# mux2.net
KiCad netlist of a schematic drawn in EAGLE
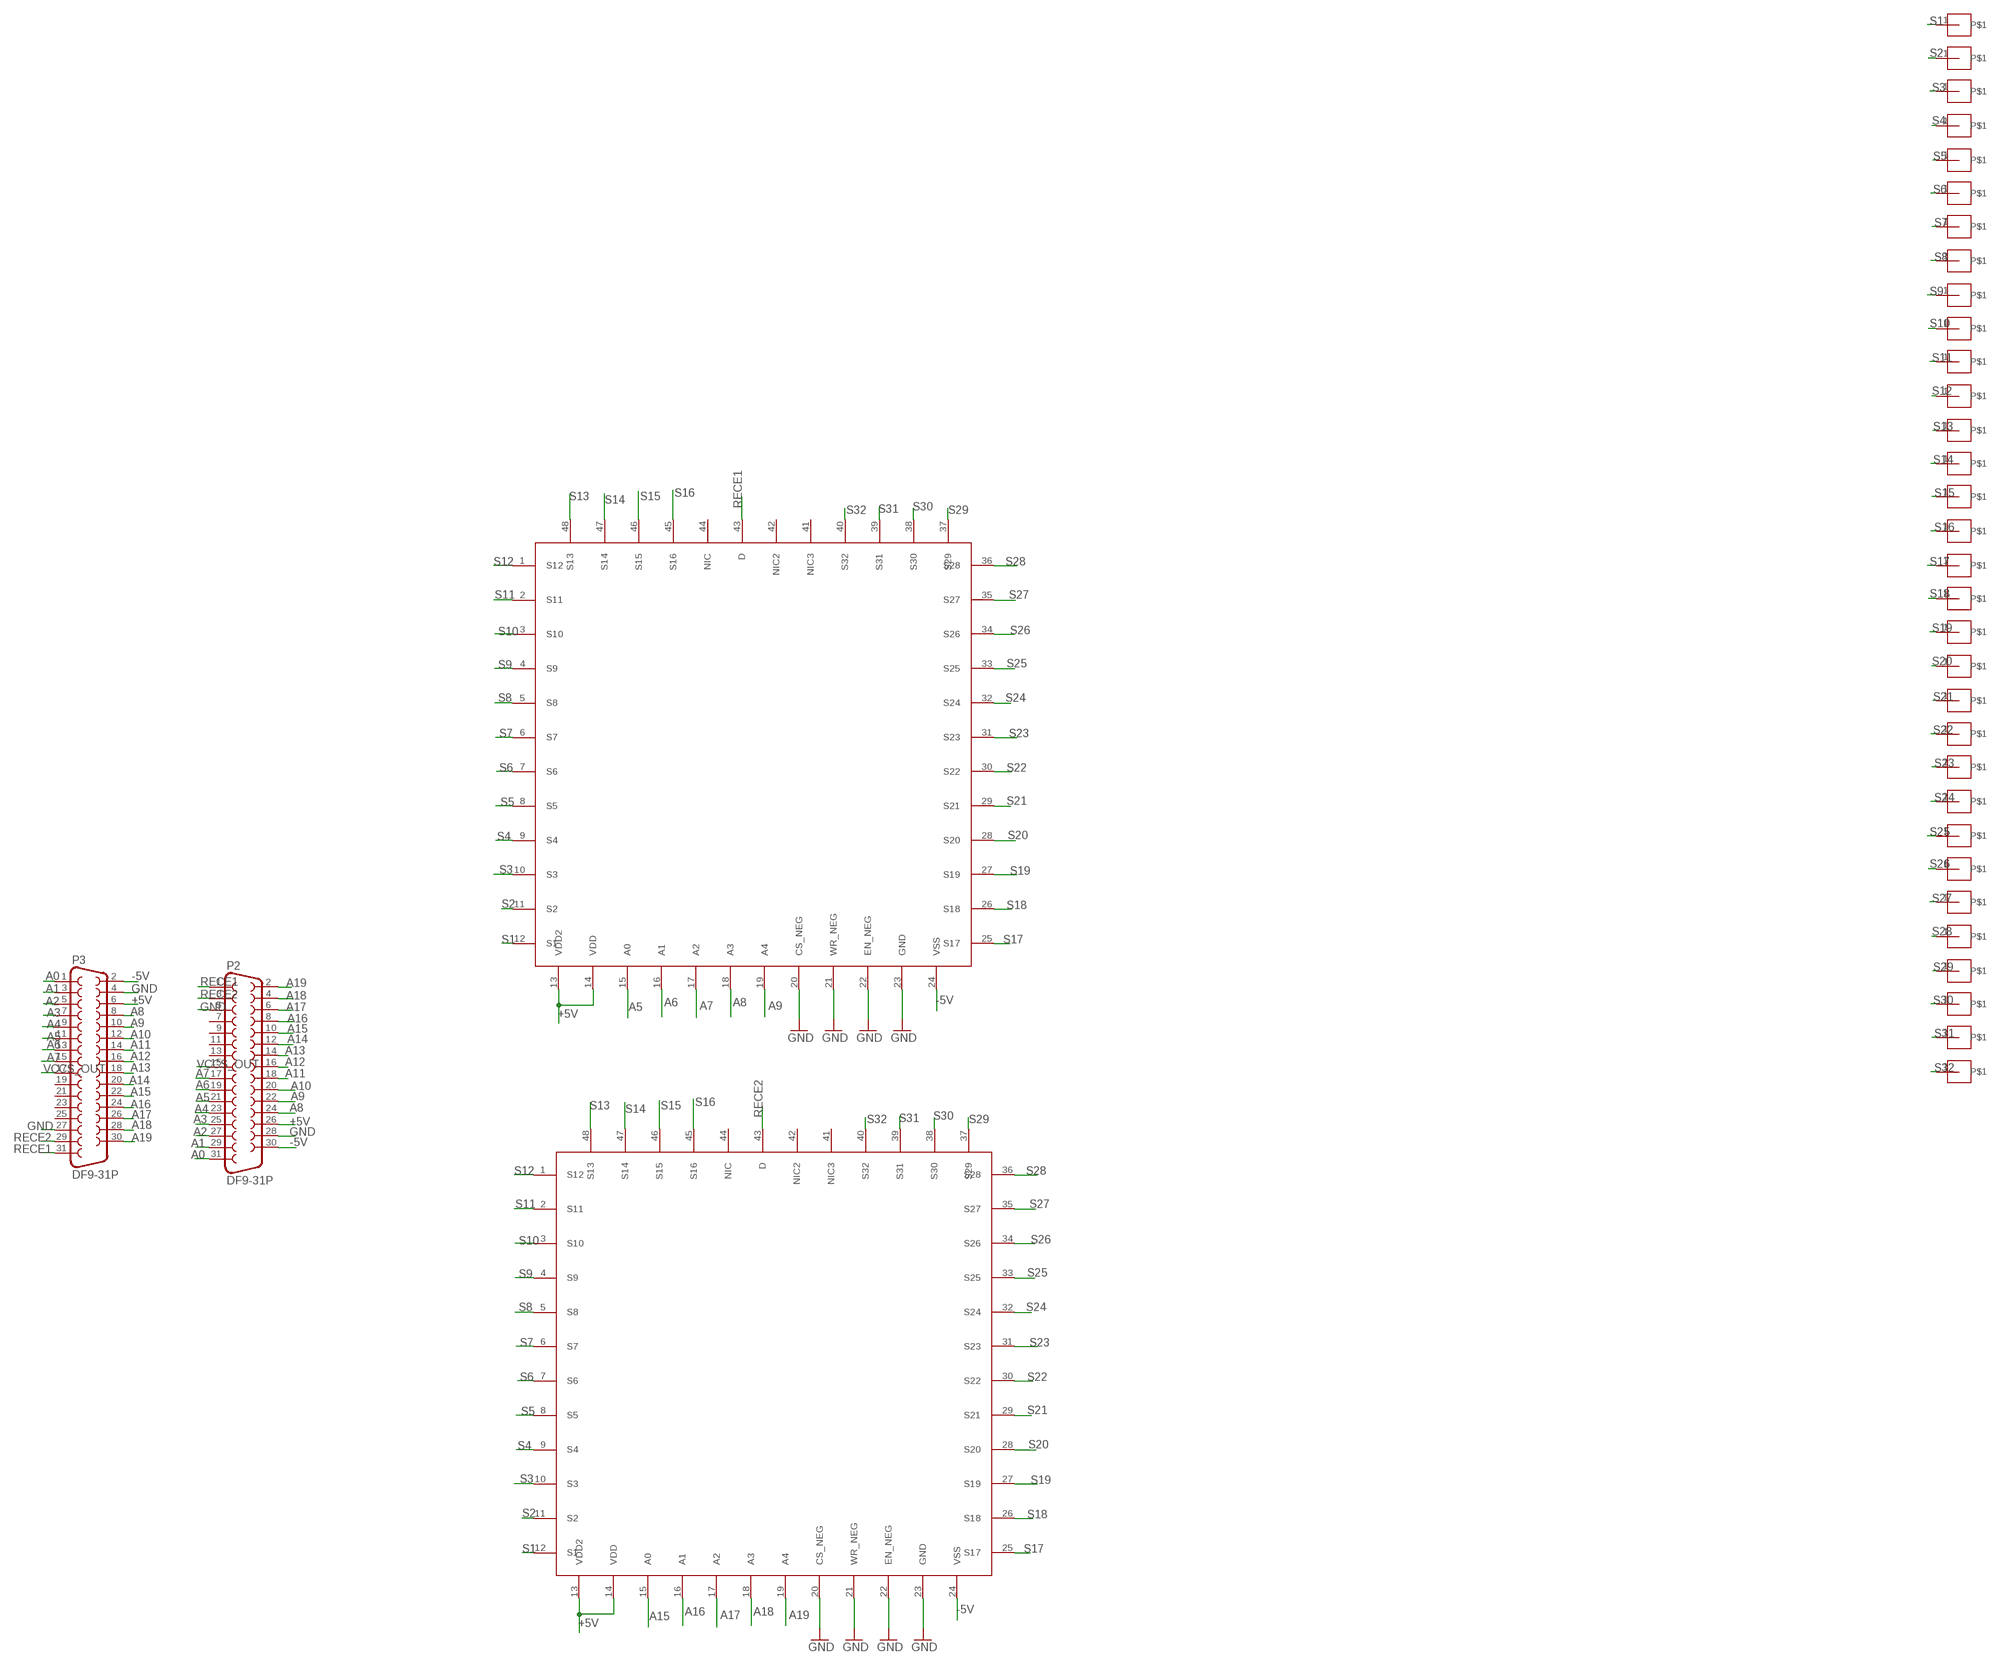
[diagram p0: schematic, sheet 1]

(export (version "E")
  (design (tool "Eeschema 10.0.6"))
  (components
    (comp (ref "P2")
      (value "DF9-31P")
      (footprint "eagle-import:DF9-31P")
      (libsource (lib "eagle-import") (part "DF9-31P"))
    )
    (comp (ref "P3")
      (value "DF9-31P")
      (footprint "eagle-import:DF9-31P")
      (libsource (lib "eagle-import") (part "DF9-31P"))
    )
    (comp (ref "U$25")
      (value "M01")
      (footprint "eagle-import:M01")
      (libsource (lib "eagle-import") (part "M01"))
    )
    (comp (ref "U$26")
      (value "M01")
      (footprint "eagle-import:M01")
      (libsource (lib "eagle-import") (part "M01"))
    )
    (comp (ref "U$27")
      (value "M01")
      (footprint "eagle-import:M01")
      (libsource (lib "eagle-import") (part "M01"))
    )
    (comp (ref "U$28")
      (value "M01")
      (footprint "eagle-import:M01")
      (libsource (lib "eagle-import") (part "M01"))
    )
    (comp (ref "U$29")
      (value "M01")
      (footprint "eagle-import:M01")
      (libsource (lib "eagle-import") (part "M01"))
    )
    (comp (ref "U$30")
      (value "M01")
      (footprint "eagle-import:M01")
      (libsource (lib "eagle-import") (part "M01"))
    )
    (comp (ref "U$31")
      (value "M01")
      (footprint "eagle-import:M01")
      (libsource (lib "eagle-import") (part "M01"))
    )
    (comp (ref "U$32")
      (value "M01")
      (footprint "eagle-import:M01")
      (libsource (lib "eagle-import") (part "M01"))
    )
    (comp (ref "U$33")
      (value "M01")
      (footprint "eagle-import:M01")
      (libsource (lib "eagle-import") (part "M01"))
    )
    (comp (ref "U$34")
      (value "M01")
      (footprint "eagle-import:M01")
      (libsource (lib "eagle-import") (part "M01"))
    )
    (comp (ref "U$35")
      (value "M01")
      (footprint "eagle-import:M01")
      (libsource (lib "eagle-import") (part "M01"))
    )
    (comp (ref "U$36")
      (value "M01")
      (footprint "eagle-import:M01")
      (libsource (lib "eagle-import") (part "M01"))
    )
    (comp (ref "U$37")
      (value "M01")
      (footprint "eagle-import:M01")
      (libsource (lib "eagle-import") (part "M01"))
    )
    (comp (ref "U$38")
      (value "M01")
      (footprint "eagle-import:M01")
      (libsource (lib "eagle-import") (part "M01"))
    )
    (comp (ref "U$39")
      (value "M01")
      (footprint "eagle-import:M01")
      (libsource (lib "eagle-import") (part "M01"))
    )
    (comp (ref "U$40")
      (value "M01")
      (footprint "eagle-import:M01")
      (libsource (lib "eagle-import") (part "M01"))
    )
    (comp (ref "U$41")
      (value "M01")
      (footprint "eagle-import:M01")
      (libsource (lib "eagle-import") (part "M01"))
    )
    (comp (ref "U$42")
      (value "M01")
      (footprint "eagle-import:M01")
      (libsource (lib "eagle-import") (part "M01"))
    )
    (comp (ref "U$43")
      (value "M01")
      (footprint "eagle-import:M01")
      (libsource (lib "eagle-import") (part "M01"))
    )
    (comp (ref "U$44")
      (value "M01")
      (footprint "eagle-import:M01")
      (libsource (lib "eagle-import") (part "M01"))
    )
    (comp (ref "U$45")
      (value "M01")
      (footprint "eagle-import:M01")
      (libsource (lib "eagle-import") (part "M01"))
    )
    (comp (ref "U$46")
      (value "M01")
      (footprint "eagle-import:M01")
      (libsource (lib "eagle-import") (part "M01"))
    )
    (comp (ref "U$47")
      (value "M01")
      (footprint "eagle-import:M01")
      (libsource (lib "eagle-import") (part "M01"))
    )
    (comp (ref "U$48")
      (value "M01")
      (footprint "eagle-import:M01")
      (libsource (lib "eagle-import") (part "M01"))
    )
    (comp (ref "U$49")
      (value "M01")
      (footprint "eagle-import:M01")
      (libsource (lib "eagle-import") (part "M01"))
    )
    (comp (ref "U$50")
      (value "M01")
      (footprint "eagle-import:M01")
      (libsource (lib "eagle-import") (part "M01"))
    )
    (comp (ref "U$51")
      (value "M01")
      (footprint "eagle-import:M01")
      (libsource (lib "eagle-import") (part "M01"))
    )
    (comp (ref "U$52")
      (value "M01")
      (footprint "eagle-import:M01")
      (libsource (lib "eagle-import") (part "M01"))
    )
    (comp (ref "U$53")
      (value "M01")
      (footprint "eagle-import:M01")
      (libsource (lib "eagle-import") (part "M01"))
    )
    (comp (ref "U$54")
      (value "M01")
      (footprint "eagle-import:M01")
      (libsource (lib "eagle-import") (part "M01"))
    )
    (comp (ref "U$55")
      (value "M01")
      (footprint "eagle-import:M01")
      (libsource (lib "eagle-import") (part "M01"))
    )
    (comp (ref "U$56")
      (value "M01")
      (footprint "eagle-import:M01")
      (libsource (lib "eagle-import") (part "M01"))
    )
    (comp (ref "U$73")
      (value "ADG732")
      (footprint "eagle-import:TQFP48")
      (libsource (lib "eagle-import") (part "ADG732"))
    )
    (comp (ref "U$74")
      (value "ADG732")
      (footprint "eagle-import:TQFP48")
      (libsource (lib "eagle-import") (part "ADG732"))
    )
  )
  (nets
    (net (code "1") (name "/+5V") (class "Default")
      (node (ref "P2") (pin "26") (pinfunction "26_26") (pintype "passive"))
      (node (ref "P3") (pin "6") (pinfunction "6_6") (pintype "passive"))
      (node (ref "U$73") (pin "13") (pinfunction "VDD2_13") (pintype "bidirectional"))
      (node (ref "U$73") (pin "14") (pinfunction "VDD_14") (pintype "bidirectional"))
      (node (ref "U$74") (pin "13") (pinfunction "VDD2_13") (pintype "bidirectional"))
      (node (ref "U$74") (pin "14") (pinfunction "VDD_14") (pintype "bidirectional"))
    )
    (net (code "2") (name "/-5V") (class "Default")
      (node (ref "P2") (pin "30") (pinfunction "30_30") (pintype "passive"))
      (node (ref "P3") (pin "2") (pinfunction "2_2") (pintype "passive"))
      (node (ref "U$73") (pin "24") (pinfunction "VSS_24") (pintype "bidirectional"))
      (node (ref "U$74") (pin "24") (pinfunction "VSS_24") (pintype "bidirectional"))
    )
    (net (code "3") (name "/A0") (class "Default")
      (node (ref "P2") (pin "31") (pinfunction "31_31") (pintype "passive"))
      (node (ref "P3") (pin "1") (pinfunction "1_1") (pintype "passive"))
    )
    (net (code "4") (name "/A1") (class "Default")
      (node (ref "P2") (pin "29") (pinfunction "29_29") (pintype "passive"))
      (node (ref "P3") (pin "3") (pinfunction "3_3") (pintype "passive"))
    )
    (net (code "5") (name "/A2") (class "Default")
      (node (ref "P2") (pin "27") (pinfunction "27_27") (pintype "passive"))
      (node (ref "P3") (pin "5") (pinfunction "5_5") (pintype "passive"))
    )
    (net (code "6") (name "/A3") (class "Default")
      (node (ref "P2") (pin "25") (pinfunction "25_25") (pintype "passive"))
      (node (ref "P3") (pin "7") (pinfunction "7_7") (pintype "passive"))
    )
    (net (code "7") (name "/A4") (class "Default")
      (node (ref "P2") (pin "23") (pinfunction "23_23") (pintype "passive"))
      (node (ref "P3") (pin "9") (pinfunction "9_9") (pintype "passive"))
    )
    (net (code "8") (name "/A5") (class "Default")
      (node (ref "P2") (pin "21") (pinfunction "21_21") (pintype "passive"))
      (node (ref "P3") (pin "11") (pinfunction "11_11") (pintype "passive"))
      (node (ref "U$74") (pin "15") (pinfunction "A0_15") (pintype "bidirectional"))
    )
    (net (code "9") (name "/A6") (class "Default")
      (node (ref "P2") (pin "19") (pinfunction "19_19") (pintype "passive"))
      (node (ref "P3") (pin "13") (pinfunction "13_13") (pintype "passive"))
      (node (ref "U$74") (pin "16") (pinfunction "A1_16") (pintype "bidirectional"))
    )
    (net (code "10") (name "/A7") (class "Default")
      (node (ref "P2") (pin "17") (pinfunction "17_17") (pintype "passive"))
      (node (ref "P3") (pin "15") (pinfunction "15_15") (pintype "passive"))
      (node (ref "U$74") (pin "17") (pinfunction "A2_17") (pintype "bidirectional"))
    )
    (net (code "11") (name "/A8") (class "Default")
      (node (ref "P2") (pin "24") (pinfunction "24_24") (pintype "passive"))
      (node (ref "P3") (pin "8") (pinfunction "8_8") (pintype "passive"))
      (node (ref "U$74") (pin "18") (pinfunction "A3_18") (pintype "bidirectional"))
    )
    (net (code "12") (name "/A9") (class "Default")
      (node (ref "P2") (pin "22") (pinfunction "22_22") (pintype "passive"))
      (node (ref "P3") (pin "10") (pinfunction "10_10") (pintype "passive"))
      (node (ref "U$74") (pin "19") (pinfunction "A4_19") (pintype "bidirectional"))
    )
    (net (code "13") (name "/A10") (class "Default")
      (node (ref "P2") (pin "20") (pinfunction "20_20") (pintype "passive"))
      (node (ref "P3") (pin "12") (pinfunction "12_12") (pintype "passive"))
    )
    (net (code "14") (name "/A11") (class "Default")
      (node (ref "P2") (pin "18") (pinfunction "18_18") (pintype "passive"))
      (node (ref "P3") (pin "14") (pinfunction "14_14") (pintype "passive"))
    )
    (net (code "15") (name "/A12") (class "Default")
      (node (ref "P2") (pin "16") (pinfunction "16_16") (pintype "passive"))
      (node (ref "P3") (pin "16") (pinfunction "16_16") (pintype "passive"))
    )
    (net (code "16") (name "/A13") (class "Default")
      (node (ref "P2") (pin "14") (pinfunction "14_14") (pintype "passive"))
      (node (ref "P3") (pin "18") (pinfunction "18_18") (pintype "passive"))
    )
    (net (code "17") (name "/A14") (class "Default")
      (node (ref "P2") (pin "12") (pinfunction "12_12") (pintype "passive"))
      (node (ref "P3") (pin "20") (pinfunction "20_20") (pintype "passive"))
    )
    (net (code "18") (name "/A15") (class "Default")
      (node (ref "P2") (pin "10") (pinfunction "10_10") (pintype "passive"))
      (node (ref "P3") (pin "22") (pinfunction "22_22") (pintype "passive"))
      (node (ref "U$73") (pin "15") (pinfunction "A0_15") (pintype "bidirectional"))
    )
    (net (code "19") (name "/A16") (class "Default")
      (node (ref "P2") (pin "8") (pinfunction "8_8") (pintype "passive"))
      (node (ref "P3") (pin "24") (pinfunction "24_24") (pintype "passive"))
      (node (ref "U$73") (pin "16") (pinfunction "A1_16") (pintype "bidirectional"))
    )
    (net (code "20") (name "/A17") (class "Default")
      (node (ref "P2") (pin "6") (pinfunction "6_6") (pintype "passive"))
      (node (ref "P3") (pin "26") (pinfunction "26_26") (pintype "passive"))
      (node (ref "U$73") (pin "17") (pinfunction "A2_17") (pintype "bidirectional"))
    )
    (net (code "21") (name "/A18") (class "Default")
      (node (ref "P2") (pin "4") (pinfunction "4_4") (pintype "passive"))
      (node (ref "P3") (pin "28") (pinfunction "28_28") (pintype "passive"))
      (node (ref "U$73") (pin "18") (pinfunction "A3_18") (pintype "bidirectional"))
    )
    (net (code "22") (name "/A19") (class "Default")
      (node (ref "P2") (pin "2") (pinfunction "2_2") (pintype "passive"))
      (node (ref "P3") (pin "30") (pinfunction "30_30") (pintype "passive"))
      (node (ref "U$73") (pin "19") (pinfunction "A4_19") (pintype "bidirectional"))
    )
    (net (code "23") (name "/RECE1") (class "Default")
      (node (ref "P2") (pin "1") (pinfunction "1_1") (pintype "passive"))
      (node (ref "P3") (pin "31") (pinfunction "31_31") (pintype "passive"))
      (node (ref "U$74") (pin "43") (pinfunction "D_43") (pintype "bidirectional"))
    )
    (net (code "24") (name "/RECE2") (class "Default")
      (node (ref "P2") (pin "3") (pinfunction "3_3") (pintype "passive"))
      (node (ref "P3") (pin "29") (pinfunction "29_29") (pintype "passive"))
      (node (ref "U$73") (pin "43") (pinfunction "D_43") (pintype "bidirectional"))
    )
    (net (code "25") (name "/S1") (class "Default")
      (node (ref "U$25") (pin "1") (pinfunction "P$1_1") (pintype "bidirectional"))
      (node (ref "U$73") (pin "12") (pinfunction "S1_12") (pintype "bidirectional"))
      (node (ref "U$74") (pin "12") (pinfunction "S1_12") (pintype "bidirectional"))
    )
    (net (code "26") (name "/S2") (class "Default")
      (node (ref "U$26") (pin "1") (pinfunction "P$1_1") (pintype "bidirectional"))
      (node (ref "U$73") (pin "11") (pinfunction "S2_11") (pintype "bidirectional"))
      (node (ref "U$74") (pin "11") (pinfunction "S2_11") (pintype "bidirectional"))
    )
    (net (code "27") (name "/S3") (class "Default")
      (node (ref "U$27") (pin "1") (pinfunction "P$1_1") (pintype "bidirectional"))
      (node (ref "U$73") (pin "10") (pinfunction "S3_10") (pintype "bidirectional"))
      (node (ref "U$74") (pin "10") (pinfunction "S3_10") (pintype "bidirectional"))
    )
    (net (code "28") (name "/S4") (class "Default")
      (node (ref "U$28") (pin "1") (pinfunction "P$1_1") (pintype "bidirectional"))
      (node (ref "U$73") (pin "9") (pinfunction "S4_9") (pintype "bidirectional"))
      (node (ref "U$74") (pin "9") (pinfunction "S4_9") (pintype "bidirectional"))
    )
    (net (code "29") (name "/S5") (class "Default")
      (node (ref "U$29") (pin "1") (pinfunction "P$1_1") (pintype "bidirectional"))
      (node (ref "U$73") (pin "8") (pinfunction "S5_8") (pintype "bidirectional"))
      (node (ref "U$74") (pin "8") (pinfunction "S5_8") (pintype "bidirectional"))
    )
    (net (code "30") (name "/S6") (class "Default")
      (node (ref "U$30") (pin "1") (pinfunction "P$1_1") (pintype "bidirectional"))
      (node (ref "U$73") (pin "7") (pinfunction "S6_7") (pintype "bidirectional"))
      (node (ref "U$74") (pin "7") (pinfunction "S6_7") (pintype "bidirectional"))
    )
    (net (code "31") (name "/S7") (class "Default")
      (node (ref "U$31") (pin "1") (pinfunction "P$1_1") (pintype "bidirectional"))
      (node (ref "U$73") (pin "6") (pinfunction "S7_6") (pintype "bidirectional"))
      (node (ref "U$74") (pin "6") (pinfunction "S7_6") (pintype "bidirectional"))
    )
    (net (code "32") (name "/S8") (class "Default")
      (node (ref "U$32") (pin "1") (pinfunction "P$1_1") (pintype "bidirectional"))
      (node (ref "U$73") (pin "5") (pinfunction "S8_5") (pintype "bidirectional"))
      (node (ref "U$74") (pin "5") (pinfunction "S8_5") (pintype "bidirectional"))
    )
    (net (code "33") (name "/S9") (class "Default")
      (node (ref "U$33") (pin "1") (pinfunction "P$1_1") (pintype "bidirectional"))
      (node (ref "U$73") (pin "4") (pinfunction "S9_4") (pintype "bidirectional"))
      (node (ref "U$74") (pin "4") (pinfunction "S9_4") (pintype "bidirectional"))
    )
    (net (code "34") (name "/S10") (class "Default")
      (node (ref "U$34") (pin "1") (pinfunction "P$1_1") (pintype "bidirectional"))
      (node (ref "U$73") (pin "3") (pinfunction "S10_3") (pintype "bidirectional"))
      (node (ref "U$74") (pin "3") (pinfunction "S10_3") (pintype "bidirectional"))
    )
    (net (code "35") (name "/S11") (class "Default")
      (node (ref "U$35") (pin "1") (pinfunction "P$1_1") (pintype "bidirectional"))
      (node (ref "U$73") (pin "2") (pinfunction "S11_2") (pintype "bidirectional"))
      (node (ref "U$74") (pin "2") (pinfunction "S11_2") (pintype "bidirectional"))
    )
    (net (code "36") (name "/S12") (class "Default")
      (node (ref "U$36") (pin "1") (pinfunction "P$1_1") (pintype "bidirectional"))
      (node (ref "U$73") (pin "1") (pinfunction "S12_1") (pintype "bidirectional"))
      (node (ref "U$74") (pin "1") (pinfunction "S12_1") (pintype "bidirectional"))
    )
    (net (code "37") (name "/S13") (class "Default")
      (node (ref "U$37") (pin "1") (pinfunction "P$1_1") (pintype "bidirectional"))
      (node (ref "U$73") (pin "48") (pinfunction "S13_48") (pintype "bidirectional"))
      (node (ref "U$74") (pin "48") (pinfunction "S13_48") (pintype "bidirectional"))
    )
    (net (code "38") (name "/S14") (class "Default")
      (node (ref "U$38") (pin "1") (pinfunction "P$1_1") (pintype "bidirectional"))
      (node (ref "U$73") (pin "47") (pinfunction "S14_47") (pintype "bidirectional"))
      (node (ref "U$74") (pin "47") (pinfunction "S14_47") (pintype "bidirectional"))
    )
    (net (code "39") (name "/S15") (class "Default")
      (node (ref "U$39") (pin "1") (pinfunction "P$1_1") (pintype "bidirectional"))
      (node (ref "U$73") (pin "46") (pinfunction "S15_46") (pintype "bidirectional"))
      (node (ref "U$74") (pin "46") (pinfunction "S15_46") (pintype "bidirectional"))
    )
    (net (code "40") (name "/S16") (class "Default")
      (node (ref "U$40") (pin "1") (pinfunction "P$1_1") (pintype "bidirectional"))
      (node (ref "U$73") (pin "45") (pinfunction "S16_45") (pintype "bidirectional"))
      (node (ref "U$74") (pin "45") (pinfunction "S16_45") (pintype "bidirectional"))
    )
    (net (code "41") (name "/S17") (class "Default")
      (node (ref "U$41") (pin "1") (pinfunction "P$1_1") (pintype "bidirectional"))
      (node (ref "U$73") (pin "25") (pinfunction "S17_25") (pintype "bidirectional"))
      (node (ref "U$74") (pin "25") (pinfunction "S17_25") (pintype "bidirectional"))
    )
    (net (code "42") (name "/S18") (class "Default")
      (node (ref "U$42") (pin "1") (pinfunction "P$1_1") (pintype "bidirectional"))
      (node (ref "U$73") (pin "26") (pinfunction "S18_26") (pintype "bidirectional"))
      (node (ref "U$74") (pin "26") (pinfunction "S18_26") (pintype "bidirectional"))
    )
    (net (code "43") (name "/S19") (class "Default")
      (node (ref "U$43") (pin "1") (pinfunction "P$1_1") (pintype "bidirectional"))
      (node (ref "U$73") (pin "27") (pinfunction "S19_27") (pintype "bidirectional"))
      (node (ref "U$74") (pin "27") (pinfunction "S19_27") (pintype "bidirectional"))
    )
    (net (code "44") (name "/S20") (class "Default")
      (node (ref "U$44") (pin "1") (pinfunction "P$1_1") (pintype "bidirectional"))
      (node (ref "U$73") (pin "28") (pinfunction "S20_28") (pintype "bidirectional"))
      (node (ref "U$74") (pin "28") (pinfunction "S20_28") (pintype "bidirectional"))
    )
    (net (code "45") (name "/S21") (class "Default")
      (node (ref "U$45") (pin "1") (pinfunction "P$1_1") (pintype "bidirectional"))
      (node (ref "U$73") (pin "29") (pinfunction "S21_29") (pintype "bidirectional"))
      (node (ref "U$74") (pin "29") (pinfunction "S21_29") (pintype "bidirectional"))
    )
    (net (code "46") (name "/S22") (class "Default")
      (node (ref "U$46") (pin "1") (pinfunction "P$1_1") (pintype "bidirectional"))
      (node (ref "U$73") (pin "30") (pinfunction "S22_30") (pintype "bidirectional"))
      (node (ref "U$74") (pin "30") (pinfunction "S22_30") (pintype "bidirectional"))
    )
    (net (code "47") (name "/S23") (class "Default")
      (node (ref "U$47") (pin "1") (pinfunction "P$1_1") (pintype "bidirectional"))
      (node (ref "U$73") (pin "31") (pinfunction "S23_31") (pintype "bidirectional"))
      (node (ref "U$74") (pin "31") (pinfunction "S23_31") (pintype "bidirectional"))
    )
    (net (code "48") (name "/S24") (class "Default")
      (node (ref "U$48") (pin "1") (pinfunction "P$1_1") (pintype "bidirectional"))
      (node (ref "U$73") (pin "32") (pinfunction "S24_32") (pintype "bidirectional"))
      (node (ref "U$74") (pin "32") (pinfunction "S24_32") (pintype "bidirectional"))
    )
    (net (code "49") (name "/S25") (class "Default")
      (node (ref "U$49") (pin "1") (pinfunction "P$1_1") (pintype "bidirectional"))
      (node (ref "U$73") (pin "33") (pinfunction "S25_33") (pintype "bidirectional"))
      (node (ref "U$74") (pin "33") (pinfunction "S25_33") (pintype "bidirectional"))
    )
    (net (code "50") (name "/S26") (class "Default")
      (node (ref "U$50") (pin "1") (pinfunction "P$1_1") (pintype "bidirectional"))
      (node (ref "U$73") (pin "34") (pinfunction "S26_34") (pintype "bidirectional"))
      (node (ref "U$74") (pin "34") (pinfunction "S26_34") (pintype "bidirectional"))
    )
    (net (code "51") (name "/S27") (class "Default")
      (node (ref "U$51") (pin "1") (pinfunction "P$1_1") (pintype "bidirectional"))
      (node (ref "U$73") (pin "35") (pinfunction "S27_35") (pintype "bidirectional"))
      (node (ref "U$74") (pin "35") (pinfunction "S27_35") (pintype "bidirectional"))
    )
    (net (code "52") (name "/S28") (class "Default")
      (node (ref "U$52") (pin "1") (pinfunction "P$1_1") (pintype "bidirectional"))
      (node (ref "U$73") (pin "36") (pinfunction "S28_36") (pintype "bidirectional"))
      (node (ref "U$74") (pin "36") (pinfunction "S28_36") (pintype "bidirectional"))
    )
    (net (code "53") (name "/S29") (class "Default")
      (node (ref "U$53") (pin "1") (pinfunction "P$1_1") (pintype "bidirectional"))
      (node (ref "U$73") (pin "37") (pinfunction "S29_37") (pintype "bidirectional"))
      (node (ref "U$74") (pin "37") (pinfunction "S29_37") (pintype "bidirectional"))
    )
    (net (code "54") (name "/S30") (class "Default")
      (node (ref "U$54") (pin "1") (pinfunction "P$1_1") (pintype "bidirectional"))
      (node (ref "U$73") (pin "38") (pinfunction "S30_38") (pintype "bidirectional"))
      (node (ref "U$74") (pin "38") (pinfunction "S30_38") (pintype "bidirectional"))
    )
    (net (code "55") (name "/S31") (class "Default")
      (node (ref "U$55") (pin "1") (pinfunction "P$1_1") (pintype "bidirectional"))
      (node (ref "U$73") (pin "39") (pinfunction "S31_39") (pintype "bidirectional"))
      (node (ref "U$74") (pin "39") (pinfunction "S31_39") (pintype "bidirectional"))
    )
    (net (code "56") (name "/S32") (class "Default")
      (node (ref "U$56") (pin "1") (pinfunction "P$1_1") (pintype "bidirectional"))
      (node (ref "U$73") (pin "40") (pinfunction "S32_40") (pintype "bidirectional"))
      (node (ref "U$74") (pin "40") (pinfunction "S32_40") (pintype "bidirectional"))
    )
    (net (code "57") (name "/VCCS_OUT") (class "Default")
      (node (ref "P2") (pin "15") (pinfunction "15_15") (pintype "passive"))
      (node (ref "P3") (pin "17") (pinfunction "17_17") (pintype "passive"))
    )
    (net (code "58") (name "GND") (class "Default")
      (node (ref "P2") (pin "28") (pinfunction "28_28") (pintype "passive"))
      (node (ref "P2") (pin "5") (pinfunction "5_5") (pintype "passive"))
      (node (ref "P3") (pin "27") (pinfunction "27_27") (pintype "passive"))
      (node (ref "P3") (pin "4") (pinfunction "4_4") (pintype "passive"))
      (node (ref "U$73") (pin "20") (pinfunction "CS_NEG_20") (pintype "bidirectional"))
      (node (ref "U$73") (pin "21") (pinfunction "WR_NEG_21") (pintype "bidirectional"))
      (node (ref "U$73") (pin "22") (pinfunction "EN_NEG_22") (pintype "bidirectional"))
      (node (ref "U$73") (pin "23") (pinfunction "GND_23") (pintype "bidirectional"))
      (node (ref "U$74") (pin "20") (pinfunction "CS_NEG_20") (pintype "bidirectional"))
      (node (ref "U$74") (pin "21") (pinfunction "WR_NEG_21") (pintype "bidirectional"))
      (node (ref "U$74") (pin "22") (pinfunction "EN_NEG_22") (pintype "bidirectional"))
      (node (ref "U$74") (pin "23") (pinfunction "GND_23") (pintype "bidirectional"))
    )
    (net (code "59") (name "unconnected-(P2-Pad7)") (class "Default")
      (node (ref "P2") (pin "7") (pinfunction "7_7") (pintype "passive"))
    )
    (net (code "60") (name "unconnected-(P2-Pad9)") (class "Default")
      (node (ref "P2") (pin "9") (pinfunction "9_9") (pintype "passive"))
    )
    (net (code "61") (name "unconnected-(P2-Pad11)") (class "Default")
      (node (ref "P2") (pin "11") (pinfunction "11_11") (pintype "passive"))
    )
    (net (code "62") (name "unconnected-(P2-Pad13)") (class "Default")
      (node (ref "P2") (pin "13") (pinfunction "13_13") (pintype "passive"))
    )
    (net (code "63") (name "unconnected-(P3-Pad19)") (class "Default")
      (node (ref "P3") (pin "19") (pinfunction "19_19") (pintype "passive"))
    )
    (net (code "64") (name "unconnected-(P3-Pad21)") (class "Default")
      (node (ref "P3") (pin "21") (pinfunction "21_21") (pintype "passive"))
    )
    (net (code "65") (name "unconnected-(P3-Pad23)") (class "Default")
      (node (ref "P3") (pin "23") (pinfunction "23_23") (pintype "passive"))
    )
    (net (code "66") (name "unconnected-(P3-Pad25)") (class "Default")
      (node (ref "P3") (pin "25") (pinfunction "25_25") (pintype "passive"))
    )
    (net (code "67") (name "unconnected-(U$73-NIC-Pad44)") (class "Default")
      (node (ref "U$73") (pin "44") (pinfunction "NIC_44") (pintype "bidirectional"))
    )
    (net (code "68") (name "unconnected-(U$73-NIC2-Pad42)") (class "Default")
      (node (ref "U$73") (pin "42") (pinfunction "NIC2_42") (pintype "bidirectional"))
    )
    (net (code "69") (name "unconnected-(U$73-NIC3-Pad41)") (class "Default")
      (node (ref "U$73") (pin "41") (pinfunction "NIC3_41") (pintype "bidirectional"))
    )
    (net (code "70") (name "unconnected-(U$74-NIC-Pad44)") (class "Default")
      (node (ref "U$74") (pin "44") (pinfunction "NIC_44") (pintype "bidirectional"))
    )
    (net (code "71") (name "unconnected-(U$74-NIC2-Pad42)") (class "Default")
      (node (ref "U$74") (pin "42") (pinfunction "NIC2_42") (pintype "bidirectional"))
    )
    (net (code "72") (name "unconnected-(U$74-NIC3-Pad41)") (class "Default")
      (node (ref "U$74") (pin "41") (pinfunction "NIC3_41") (pintype "bidirectional"))
    )
  )
)
